# trx-breakout.net
KiCad netlist of a schematic drawn in EAGLE
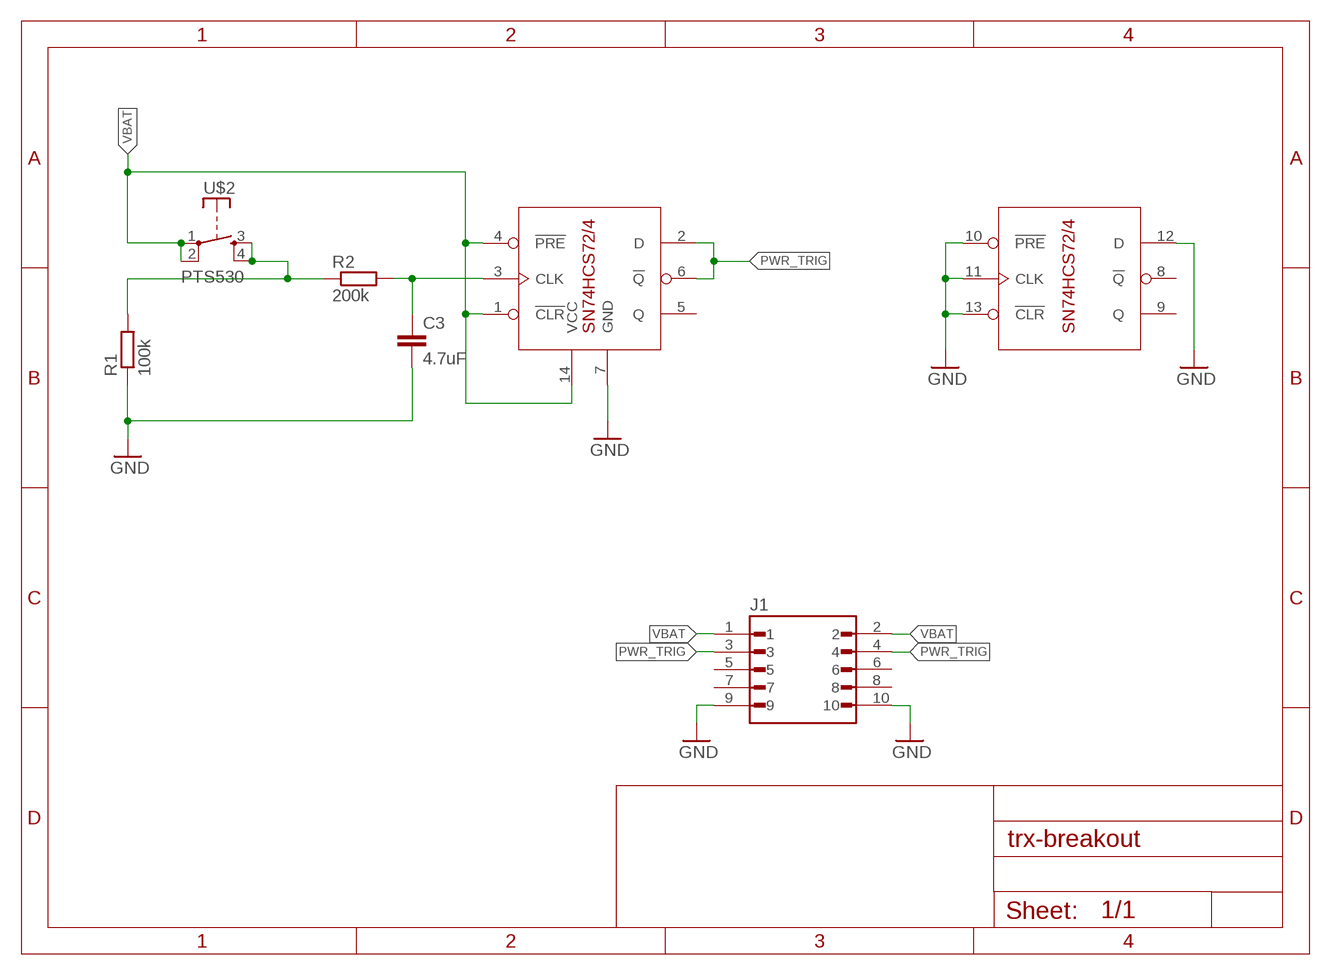
[diagram p0: schematic, sheet 1]

(export (version "E")
  (design (tool "Eeschema 10.0.6"))
  (components
    (comp (ref "C3")
      (value "4.7uF")
      (footprint "eagle-import:C0805")
      (libsource (lib "eagle-import") (part "C-EUC0805"))
    )
    (comp (ref "J1")
      (value "DF12NB(3.0)-10DX-0.5VHRS_DF12NB(3.0)-10DS-0.5V")
      (footprint "eagle-import:HRS_DF12NB(3.0)-10DS-0.5V")
      (libsource (lib "eagle-import") (part "DF12NB(3.0)-10DX-0.5VHRS_DF12NB(3.0)-10DS-0.5V"))
    )
    (comp (ref "R1")
      (value "100k")
      (footprint "eagle-import:R0805")
      (libsource (lib "eagle-import") (part "R-EU_R0805"))
    )
    (comp (ref "R2")
      (value "200k")
      (footprint "eagle-import:R0805")
      (libsource (lib "eagle-import") (part "R-EU_R0805"))
    )
    (comp (ref "U$1")
      (value "SN74HCS72/4")
      (footprint "eagle-import:TSSOP14")
      (libsource (lib "eagle-import") (part "SN74HCS72/4"))
    )
    (comp (ref "U$2")
      (value "PTS530")
      (footprint "eagle-import:PTS530")
      (libsource (lib "eagle-import") (part "PTS530"))
    )
  )
  (nets
    (net (code "1") (name "GND") (class "Default")
      (node (ref "C3") (pin "2") (pinfunction "2_2") (pintype "passive"))
      (node (ref "J1") (pin "10") (pinfunction "10_10") (pintype "passive"))
      (node (ref "J1") (pin "9") (pinfunction "9_9") (pintype "passive"))
      (node (ref "R1") (pin "1") (pinfunction "1_1") (pintype "passive"))
      (node (ref "U$1") (pin "10") (pinfunction "~{PRE}_10") (pintype "input"))
      (node (ref "U$1") (pin "11") (pinfunction "CLK_11") (pintype "input"))
      (node (ref "U$1") (pin "12") (pinfunction "D_12") (pintype "input"))
      (node (ref "U$1") (pin "13") (pinfunction "~{CLR}_13") (pintype "input"))
      (node (ref "U$1") (pin "7") (pinfunction "GND_7") (pintype "bidirectional"))
    )
    (net (code "2") (name "Net-(R1-Pad2)") (class "Default")
      (node (ref "R1") (pin "2") (pinfunction "2_2") (pintype "passive"))
      (node (ref "R2") (pin "1") (pinfunction "1_1") (pintype "passive"))
      (node (ref "U$2") (pin "3") (pinfunction "S_3") (pintype "passive"))
      (node (ref "U$2") (pin "4") (pinfunction "S_4") (pintype "passive"))
    )
    (net (code "3") (name "Net-(U$1A-CLK)") (class "Default")
      (node (ref "C3") (pin "1") (pinfunction "1_1") (pintype "passive"))
      (node (ref "R2") (pin "2") (pinfunction "2_2") (pintype "passive"))
      (node (ref "U$1") (pin "3") (pinfunction "CLK_3") (pintype "input"))
    )
    (net (code "4") (name "PWR_TRIG") (class "Default")
      (node (ref "J1") (pin "3") (pinfunction "3_3") (pintype "passive"))
      (node (ref "J1") (pin "4") (pinfunction "4_4") (pintype "passive"))
      (node (ref "U$1") (pin "2") (pinfunction "D_2") (pintype "input"))
      (node (ref "U$1") (pin "6") (pinfunction "~{Q}_6") (pintype "output"))
    )
    (net (code "5") (name "VBAT") (class "Default")
      (node (ref "J1") (pin "1") (pinfunction "1_1") (pintype "passive"))
      (node (ref "J1") (pin "2") (pinfunction "2_2") (pintype "passive"))
      (node (ref "U$1") (pin "1") (pinfunction "~{CLR}_1") (pintype "input"))
      (node (ref "U$1") (pin "14") (pinfunction "VCC_14") (pintype "power_in"))
      (node (ref "U$1") (pin "4") (pinfunction "~{PRE}_4") (pintype "input"))
      (node (ref "U$2") (pin "1") (pinfunction "P_1") (pintype "passive"))
      (node (ref "U$2") (pin "2") (pinfunction "P_2") (pintype "passive"))
    )
    (net (code "6") (name "unconnected-(J1-Pad5)") (class "Default")
      (node (ref "J1") (pin "5") (pinfunction "5_5") (pintype "passive"))
    )
    (net (code "7") (name "unconnected-(J1-Pad6)") (class "Default")
      (node (ref "J1") (pin "6") (pinfunction "6_6") (pintype "passive"))
    )
    (net (code "8") (name "unconnected-(J1-Pad7)") (class "Default")
      (node (ref "J1") (pin "7") (pinfunction "7_7") (pintype "passive"))
    )
    (net (code "9") (name "unconnected-(J1-Pad8)") (class "Default")
      (node (ref "J1") (pin "8") (pinfunction "8_8") (pintype "passive"))
    )
    (net (code "10") (name "unconnected-(U$1A-Q-Pad5)") (class "Default")
      (node (ref "U$1") (pin "5") (pinfunction "Q_5") (pintype "output"))
    )
    (net (code "11") (name "unconnected-(U$1B-Q-Pad9)") (class "Default")
      (node (ref "U$1") (pin "9") (pinfunction "Q_9") (pintype "output"))
    )
    (net (code "12") (name "unconnected-(U$1B-~{Q}-Pad8)") (class "Default")
      (node (ref "U$1") (pin "8") (pinfunction "~{Q}_8") (pintype "output"))
    )
  )
)
